# PE10.net
KiCad netlist of a schematic drawn in EAGLE
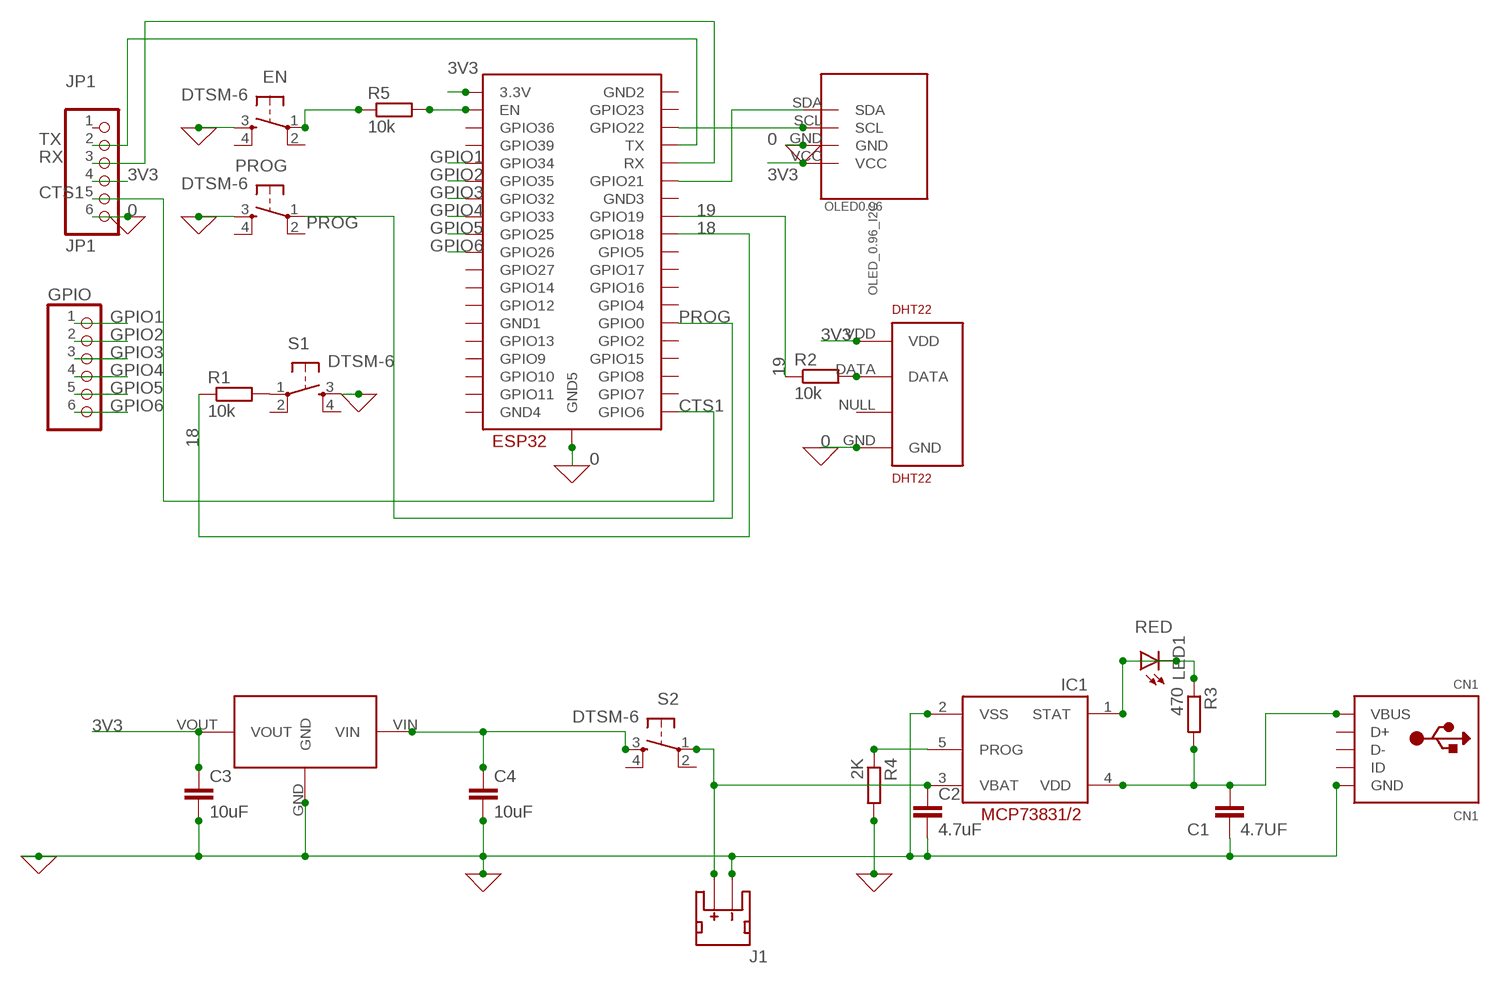
[diagram p0: schematic, sheet 1]

(export (version "E")
  (design (tool "Eeschema 10.0.6"))
  (components
    (comp (ref "C1")
      (value "4.7UF")
      (footprint "eagle-import:C1812K")
      (libsource (lib "eagle-import") (part "C-EUC1812K"))
    )
    (comp (ref "C2")
      (value "4.7uF")
      (footprint "eagle-import:C1812K")
      (libsource (lib "eagle-import") (part "C-EUC1812K"))
    )
    (comp (ref "C3")
      (value "10uF")
      (footprint "eagle-import:C1812K")
      (libsource (lib "eagle-import") (part "C-EUC1812K"))
    )
    (comp (ref "C4")
      (value "10uF")
      (footprint "eagle-import:C1812K")
      (libsource (lib "eagle-import") (part "C-EUC1812K"))
    )
    (comp (ref "CN1")
      (value "CN1")
      (footprint "eagle-import:USB-MINIB")
      (libsource (lib "eagle-import") (part "USBMINIB"))
    )
    (comp (ref "DHT22")
      (value "DHT22")
      (footprint "eagle-import:RHT03_DHT-22")
      (libsource (lib "eagle-import") (part "RHT03_DHT-22_AM2302"))
    )
    (comp (ref "EN")
      (value "DTSM-6")
      (footprint "eagle-import:DTSM-6")
      (libsource (lib "eagle-import") (part "DTSM-6"))
    )
    (comp (ref "GPIO")
      (value "PINHD-1X6")
      (footprint "eagle-import:1X06")
      (libsource (lib "eagle-import") (part "PINHD-1X6"))
    )
    (comp (ref "HT7333-7")
      (value "HT7333")
      (footprint "eagle-import:SOT89")
      (libsource (lib "eagle-import") (part "HT7333"))
    )
    (comp (ref "IC1")
      (value "MCP73831/OT")
      (footprint "eagle-import:SOT23-5L")
      (libsource (lib "eagle-import") (part "MCP73831/OT"))
    )
    (comp (ref "J1")
      (value "5V")
      (footprint "eagle-import:JST-2-SMD")
      (libsource (lib "eagle-import") (part "JST_2MM_MALE"))
    )
    (comp (ref "JP1")
      (value "JP1")
      (footprint "eagle-import:1X06")
      (libsource (lib "eagle-import") (part "adafruit_420_PINHD-1X6"))
    )
    (comp (ref "LED1")
      (value "RED")
      (footprint "eagle-import:SMART-LED")
      (libsource (lib "eagle-import") (part "LEDSMART-LED"))
    )
    (comp (ref "OLED0.96")
      (value "OLED_0.96_I2C")
      (footprint "eagle-import:OLED_0.96_I2C")
      (libsource (lib "eagle-import") (part "OLED_0.96_I2C"))
    )
    (comp (ref "PROG")
      (value "DTSM-6")
      (footprint "eagle-import:DTSM-6")
      (libsource (lib "eagle-import") (part "DTSM-6"))
    )
    (comp (ref "R1")
      (value "10k")
      (footprint "eagle-import:R1206W")
      (libsource (lib "eagle-import") (part "R-EU_R1206W"))
    )
    (comp (ref "R2")
      (value "10k")
      (footprint "eagle-import:R1206W")
      (libsource (lib "eagle-import") (part "R-EU_R1206W"))
    )
    (comp (ref "R3")
      (value "470")
      (footprint "eagle-import:R1206W")
      (libsource (lib "eagle-import") (part "R-EU_R1206W"))
    )
    (comp (ref "R4")
      (value "2K")
      (footprint "eagle-import:R1206W")
      (libsource (lib "eagle-import") (part "R-EU_R1206W"))
    )
    (comp (ref "R5")
      (value "10k")
      (footprint "eagle-import:R1206W")
      (libsource (lib "eagle-import") (part "R-EU_R1206W"))
    )
    (comp (ref "S1")
      (value "DTSM-6")
      (footprint "eagle-import:DTSM-6")
      (libsource (lib "eagle-import") (part "DTSM-6"))
    )
    (comp (ref "S2")
      (value "DTSM-6")
      (footprint "eagle-import:DTSM-6")
      (libsource (lib "eagle-import") (part "DTSM-6"))
    )
    (comp (ref "U$1")
      (value "ESP32-WROOM")
      (footprint "eagle-import:ESP32-WROOM")
      (libsource (lib "eagle-import") (part "ESP32-WROOM"))
    )
  )
  (nets
    (net (code "1") (name "/3V3") (class "Default")
      (node (ref "C3") (pin "1") (pinfunction "1_1") (pintype "passive"))
      (node (ref "DHT22") (pin "VDD") (pinfunction "VDD_VDD") (pintype "power_in"))
      (node (ref "HT7333-7") (pin "VOUT") (pinfunction "VOUT_VOUT") (pintype "bidirectional"))
      (node (ref "JP1") (pin "4") (pinfunction "4_4") (pintype "passive"))
      (node (ref "OLED0.96") (pin "VCC") (pinfunction "VCC_VCC") (pintype "bidirectional"))
      (node (ref "U$1") (pin "3V3") (pinfunction "3.3V_3V3") (pintype "bidirectional"))
    )
    (net (code "2") (name "/18") (class "Default")
      (node (ref "R1") (pin "1") (pinfunction "1_1") (pintype "passive"))
      (node (ref "U$1") (pin "IO18") (pinfunction "GPIO18_IO18") (pintype "bidirectional"))
    )
    (net (code "3") (name "/19") (class "Default")
      (node (ref "R2") (pin "1") (pinfunction "1_1") (pintype "passive"))
      (node (ref "U$1") (pin "IO19") (pinfunction "GPIO19_IO19") (pintype "bidirectional"))
    )
    (net (code "4") (name "/CTS1") (class "Default")
      (node (ref "JP1") (pin "5") (pinfunction "5_5") (pintype "passive"))
      (node (ref "U$1") (pin "CLK") (pinfunction "GPIO6_CLK") (pintype "bidirectional"))
    )
    (net (code "5") (name "/GPIO1") (class "Default")
      (node (ref "GPIO") (pin "1") (pinfunction "1_1") (pintype "passive"))
      (node (ref "U$1") (pin "IO34") (pinfunction "GPIO34_IO34") (pintype "bidirectional"))
    )
    (net (code "6") (name "/GPIO2") (class "Default")
      (node (ref "GPIO") (pin "2") (pinfunction "2_2") (pintype "passive"))
      (node (ref "U$1") (pin "IO35") (pinfunction "GPIO35_IO35") (pintype "bidirectional"))
    )
    (net (code "7") (name "/GPIO3") (class "Default")
      (node (ref "GPIO") (pin "3") (pinfunction "3_3") (pintype "passive"))
      (node (ref "U$1") (pin "IO32") (pinfunction "GPIO32_IO32") (pintype "bidirectional"))
    )
    (net (code "8") (name "/GPIO4") (class "Default")
      (node (ref "GPIO") (pin "4") (pinfunction "4_4") (pintype "passive"))
      (node (ref "U$1") (pin "IO33") (pinfunction "GPIO33_IO33") (pintype "bidirectional"))
    )
    (net (code "9") (name "/GPIO5") (class "Default")
      (node (ref "GPIO") (pin "5") (pinfunction "5_5") (pintype "passive"))
      (node (ref "U$1") (pin "IO25") (pinfunction "GPIO25_IO25") (pintype "bidirectional"))
    )
    (net (code "10") (name "/GPIO6") (class "Default")
      (node (ref "GPIO") (pin "6") (pinfunction "6_6") (pintype "passive"))
      (node (ref "U$1") (pin "IO26") (pinfunction "GPIO26_IO26") (pintype "bidirectional"))
    )
    (net (code "11") (name "/PROG") (class "Default")
      (node (ref "PROG") (pin "1") (pinfunction "1_1") (pintype "passive"))
      (node (ref "U$1") (pin "IO0") (pinfunction "GPIO0_IO0") (pintype "bidirectional"))
    )
    (net (code "12") (name "/RX") (class "Default")
      (node (ref "JP1") (pin "3") (pinfunction "3_3") (pintype "passive"))
      (node (ref "U$1") (pin "RX") (pinfunction "RX_RX") (pintype "bidirectional"))
    )
    (net (code "13") (name "/TX") (class "Default")
      (node (ref "JP1") (pin "2") (pinfunction "2_2") (pintype "passive"))
      (node (ref "U$1") (pin "TX") (pinfunction "TX_TX") (pintype "bidirectional"))
    )
    (net (code "14") (name "GND") (class "Default")
      (node (ref "C1") (pin "2") (pinfunction "2_2") (pintype "passive"))
      (node (ref "C2") (pin "2") (pinfunction "2_2") (pintype "passive"))
      (node (ref "C3") (pin "2") (pinfunction "2_2") (pintype "passive"))
      (node (ref "C4") (pin "2") (pinfunction "2_2") (pintype "passive"))
      (node (ref "CN1") (pin "GND") (pinfunction "GND_GND") (pintype "power_in"))
      (node (ref "DHT22") (pin "GND") (pinfunction "GND_GND") (pintype "power_in"))
      (node (ref "EN") (pin "3") (pinfunction "3_3") (pintype "passive"))
      (node (ref "HT7333-7") (pin "GND") (pinfunction "GND_GND") (pintype "bidirectional"))
      (node (ref "IC1") (pin "2") (pinfunction "VSS_2") (pintype "power_in"))
      (node (ref "J1") (pin "1") (pinfunction "-_1") (pintype "bidirectional"))
      (node (ref "JP1") (pin "6") (pinfunction "6_6") (pintype "passive"))
      (node (ref "OLED0.96") (pin "GND") (pinfunction "GND_GND") (pintype "bidirectional"))
      (node (ref "PROG") (pin "3") (pinfunction "3_3") (pintype "passive"))
      (node (ref "R4") (pin "2") (pinfunction "2_2") (pintype "passive"))
      (node (ref "S1") (pin "3") (pinfunction "3_3") (pintype "passive"))
      (node (ref "U$1") (pin "GND5") (pinfunction "GND5_GND5") (pintype "bidirectional"))
    )
    (net (code "15") (name "Net-(C4-Pad1)") (class "Default")
      (node (ref "C4") (pin "1") (pinfunction "1_1") (pintype "passive"))
      (node (ref "HT7333-7") (pin "VIN") (pinfunction "VIN_VIN") (pintype "bidirectional"))
      (node (ref "S2") (pin "3") (pinfunction "3_3") (pintype "passive"))
    )
    (net (code "16") (name "Net-(DHT22-PadDATA)") (class "Default")
      (node (ref "DHT22") (pin "DATA") (pinfunction "DATA_DATA") (pintype "bidirectional"))
      (node (ref "R2") (pin "2") (pinfunction "2_2") (pintype "passive"))
    )
    (net (code "17") (name "Net-(EN-Pad1)") (class "Default")
      (node (ref "EN") (pin "1") (pinfunction "1_1") (pintype "passive"))
      (node (ref "R5") (pin "1") (pinfunction "1_1") (pintype "passive"))
    )
    (net (code "18") (name "Net-(IC1-PROG)") (class "Default")
      (node (ref "IC1") (pin "5") (pinfunction "PROG_5") (pintype "input"))
      (node (ref "R4") (pin "1") (pinfunction "1_1") (pintype "passive"))
    )
    (net (code "19") (name "Net-(IC1-STAT)") (class "Default")
      (node (ref "IC1") (pin "1") (pinfunction "STAT_1") (pintype "output"))
      (node (ref "LED1") (pin "A") (pinfunction "A_A") (pintype "passive"))
      (node (ref "LED1") (pin "B") (pinfunction "C_B") (pintype "passive"))
      (node (ref "R3") (pin "1") (pinfunction "1_1") (pintype "passive"))
    )
    (net (code "20") (name "Net-(IC1-VBAT)") (class "Default")
      (node (ref "C2") (pin "1") (pinfunction "1_1") (pintype "passive"))
      (node (ref "IC1") (pin "3") (pinfunction "VBAT_3") (pintype "bidirectional"))
      (node (ref "J1") (pin "2") (pinfunction "+_2") (pintype "bidirectional"))
      (node (ref "S2") (pin "1") (pinfunction "1_1") (pintype "passive"))
    )
    (net (code "21") (name "Net-(IC1-VDD)") (class "Default")
      (node (ref "C1") (pin "1") (pinfunction "1_1") (pintype "passive"))
      (node (ref "CN1") (pin "VBUS") (pinfunction "VBUS_VBUS") (pintype "power_in"))
      (node (ref "IC1") (pin "4") (pinfunction "VDD_4") (pintype "power_in"))
      (node (ref "R3") (pin "2") (pinfunction "2_2") (pintype "passive"))
    )
    (net (code "22") (name "Net-(R1-Pad2)") (class "Default")
      (node (ref "R1") (pin "2") (pinfunction "2_2") (pintype "passive"))
      (node (ref "S1") (pin "1") (pinfunction "1_1") (pintype "passive"))
    )
    (net (code "23") (name "Net-(R5-Pad2)") (class "Default")
      (node (ref "R5") (pin "2") (pinfunction "2_2") (pintype "passive"))
      (node (ref "U$1") (pin "EN") (pinfunction "EN_EN") (pintype "bidirectional"))
    )
    (net (code "24") (name "Net-(U$1-GPIO21)") (class "Default")
      (node (ref "OLED0.96") (pin "SDA") (pinfunction "SDA_SDA") (pintype "bidirectional"))
      (node (ref "U$1") (pin "IO21") (pinfunction "GPIO21_IO21") (pintype "bidirectional"))
    )
    (net (code "25") (name "Net-(U$1-GPIO22)") (class "Default")
      (node (ref "OLED0.96") (pin "SCL") (pinfunction "SCL_SCL") (pintype "bidirectional"))
      (node (ref "U$1") (pin "IO22") (pinfunction "GPIO22_IO22") (pintype "bidirectional"))
    )
    (net (code "26") (name "unconnected-(CN1-PadD+)") (class "Default")
      (node (ref "CN1") (pin "D+") (pinfunction "D+_D+") (pintype "bidirectional"))
    )
    (net (code "27") (name "unconnected-(CN1-PadD-)") (class "Default")
      (node (ref "CN1") (pin "D-") (pinfunction "D-_D-") (pintype "bidirectional"))
    )
    (net (code "28") (name "unconnected-(CN1-PadID)") (class "Default")
      (node (ref "CN1") (pin "ID") (pinfunction "ID_ID") (pintype "bidirectional"))
    )
    (net (code "29") (name "unconnected-(DHT22-PadNULL)") (class "Default")
      (node (ref "DHT22") (pin "NULL") (pinfunction "NULL_NULL") (pintype "no_connect"))
    )
    (net (code "30") (name "unconnected-(EN-Pad2)") (class "Default")
      (node (ref "EN") (pin "2") (pinfunction "2_2") (pintype "passive"))
    )
    (net (code "31") (name "unconnected-(EN-Pad4)") (class "Default")
      (node (ref "EN") (pin "4") (pinfunction "4_4") (pintype "passive"))
    )
    (net (code "32") (name "unconnected-(J1-PAD1-PadNC1)") (class "Default")
      (node (ref "J1") (pin "NC1") (pinfunction "PAD1_NC1") (pintype "bidirectional"))
    )
    (net (code "33") (name "unconnected-(J1-PAD2-PadNC2)") (class "Default")
      (node (ref "J1") (pin "NC2") (pinfunction "PAD2_NC2") (pintype "bidirectional"))
    )
    (net (code "34") (name "unconnected-(JP1-Pad1)") (class "Default")
      (node (ref "JP1") (pin "1") (pinfunction "1_1") (pintype "passive"))
    )
    (net (code "35") (name "unconnected-(PROG-Pad2)") (class "Default")
      (node (ref "PROG") (pin "2") (pinfunction "2_2") (pintype "passive"))
    )
    (net (code "36") (name "unconnected-(PROG-Pad4)") (class "Default")
      (node (ref "PROG") (pin "4") (pinfunction "4_4") (pintype "passive"))
    )
    (net (code "37") (name "unconnected-(S1-Pad2)") (class "Default")
      (node (ref "S1") (pin "2") (pinfunction "2_2") (pintype "passive"))
    )
    (net (code "38") (name "unconnected-(S1-Pad4)") (class "Default")
      (node (ref "S1") (pin "4") (pinfunction "4_4") (pintype "passive"))
    )
    (net (code "39") (name "unconnected-(S2-Pad2)") (class "Default")
      (node (ref "S2") (pin "2") (pinfunction "2_2") (pintype "passive"))
    )
    (net (code "40") (name "unconnected-(S2-Pad4)") (class "Default")
      (node (ref "S2") (pin "4") (pinfunction "4_4") (pintype "passive"))
    )
    (net (code "41") (name "unconnected-(U$1-GPIO2-PadIO2)") (class "Default")
      (node (ref "U$1") (pin "IO2") (pinfunction "GPIO2_IO2") (pintype "bidirectional"))
    )
    (net (code "42") (name "unconnected-(U$1-GPIO4-PadIO4)") (class "Default")
      (node (ref "U$1") (pin "IO4") (pinfunction "GPIO4_IO4") (pintype "bidirectional"))
    )
    (net (code "43") (name "unconnected-(U$1-GPIO5-PadIO5)") (class "Default")
      (node (ref "U$1") (pin "IO5") (pinfunction "GPIO5_IO5") (pintype "bidirectional"))
    )
    (net (code "44") (name "unconnected-(U$1-GPIO7-PadSD0)") (class "Default")
      (node (ref "U$1") (pin "SD0") (pinfunction "GPIO7_SD0") (pintype "bidirectional"))
    )
    (net (code "45") (name "unconnected-(U$1-GPIO8-PadSD1)") (class "Default")
      (node (ref "U$1") (pin "SD1") (pinfunction "GPIO8_SD1") (pintype "bidirectional"))
    )
    (net (code "46") (name "unconnected-(U$1-GPIO9-PadSD2)") (class "Default")
      (node (ref "U$1") (pin "SD2") (pinfunction "GPIO9_SD2") (pintype "bidirectional"))
    )
    (net (code "47") (name "unconnected-(U$1-GPIO10-PadSD3)") (class "Default")
      (node (ref "U$1") (pin "SD3") (pinfunction "GPIO10_SD3") (pintype "bidirectional"))
    )
    (net (code "48") (name "unconnected-(U$1-GPIO11-PadCMD)") (class "Default")
      (node (ref "U$1") (pin "CMD") (pinfunction "GPIO11_CMD") (pintype "bidirectional"))
    )
    (net (code "49") (name "unconnected-(U$1-GPIO12-PadIO12)") (class "Default")
      (node (ref "U$1") (pin "IO12") (pinfunction "GPIO12_IO12") (pintype "bidirectional"))
    )
    (net (code "50") (name "unconnected-(U$1-GPIO13-PadIO13)") (class "Default")
      (node (ref "U$1") (pin "IO13") (pinfunction "GPIO13_IO13") (pintype "bidirectional"))
    )
    (net (code "51") (name "unconnected-(U$1-GPIO14-PadIO14)") (class "Default")
      (node (ref "U$1") (pin "IO14") (pinfunction "GPIO14_IO14") (pintype "bidirectional"))
    )
    (net (code "52") (name "unconnected-(U$1-GPIO15-PadIO15)") (class "Default")
      (node (ref "U$1") (pin "IO15") (pinfunction "GPIO15_IO15") (pintype "bidirectional"))
    )
    (net (code "53") (name "unconnected-(U$1-GPIO16-PadIO16)") (class "Default")
      (node (ref "U$1") (pin "IO16") (pinfunction "GPIO16_IO16") (pintype "bidirectional"))
    )
    (net (code "54") (name "unconnected-(U$1-GPIO17-PadIO17)") (class "Default")
      (node (ref "U$1") (pin "IO17") (pinfunction "GPIO17_IO17") (pintype "bidirectional"))
    )
    (net (code "55") (name "unconnected-(U$1-GPIO23-PadIO23)") (class "Default")
      (node (ref "U$1") (pin "IO23") (pinfunction "GPIO23_IO23") (pintype "bidirectional"))
    )
    (net (code "56") (name "unconnected-(U$1-GPIO27-PadIO27)") (class "Default")
      (node (ref "U$1") (pin "IO27") (pinfunction "GPIO27_IO27") (pintype "bidirectional"))
    )
    (net (code "57") (name "unconnected-(U$1-GPIO36-PadSENSOR_VP)") (class "Default")
      (node (ref "U$1") (pin "SENSOR_VP") (pinfunction "GPIO36_SENSOR_VP") (pintype "bidirectional"))
    )
    (net (code "58") (name "unconnected-(U$1-GPIO39-PadSENSOR_VN)") (class "Default")
      (node (ref "U$1") (pin "SENSOR_VN") (pinfunction "GPIO39_SENSOR_VN") (pintype "bidirectional"))
    )
    (net (code "59") (name "unconnected-(U$1-PadGND1)") (class "Default")
      (node (ref "U$1") (pin "GND1") (pinfunction "GND1_GND1") (pintype "bidirectional"))
    )
    (net (code "60") (name "unconnected-(U$1-PadGND2)") (class "Default")
      (node (ref "U$1") (pin "GND2") (pinfunction "GND2_GND2") (pintype "bidirectional"))
    )
    (net (code "61") (name "unconnected-(U$1-PadGND3)") (class "Default")
      (node (ref "U$1") (pin "GND3") (pinfunction "GND3_GND3") (pintype "bidirectional"))
    )
    (net (code "62") (name "unconnected-(U$1-PadGND4)") (class "Default")
      (node (ref "U$1") (pin "GND4") (pinfunction "GND4_GND4") (pintype "bidirectional"))
    )
  )
)
